# Extruder_0_Board.net
KiCad netlist of a schematic drawn in EAGLE
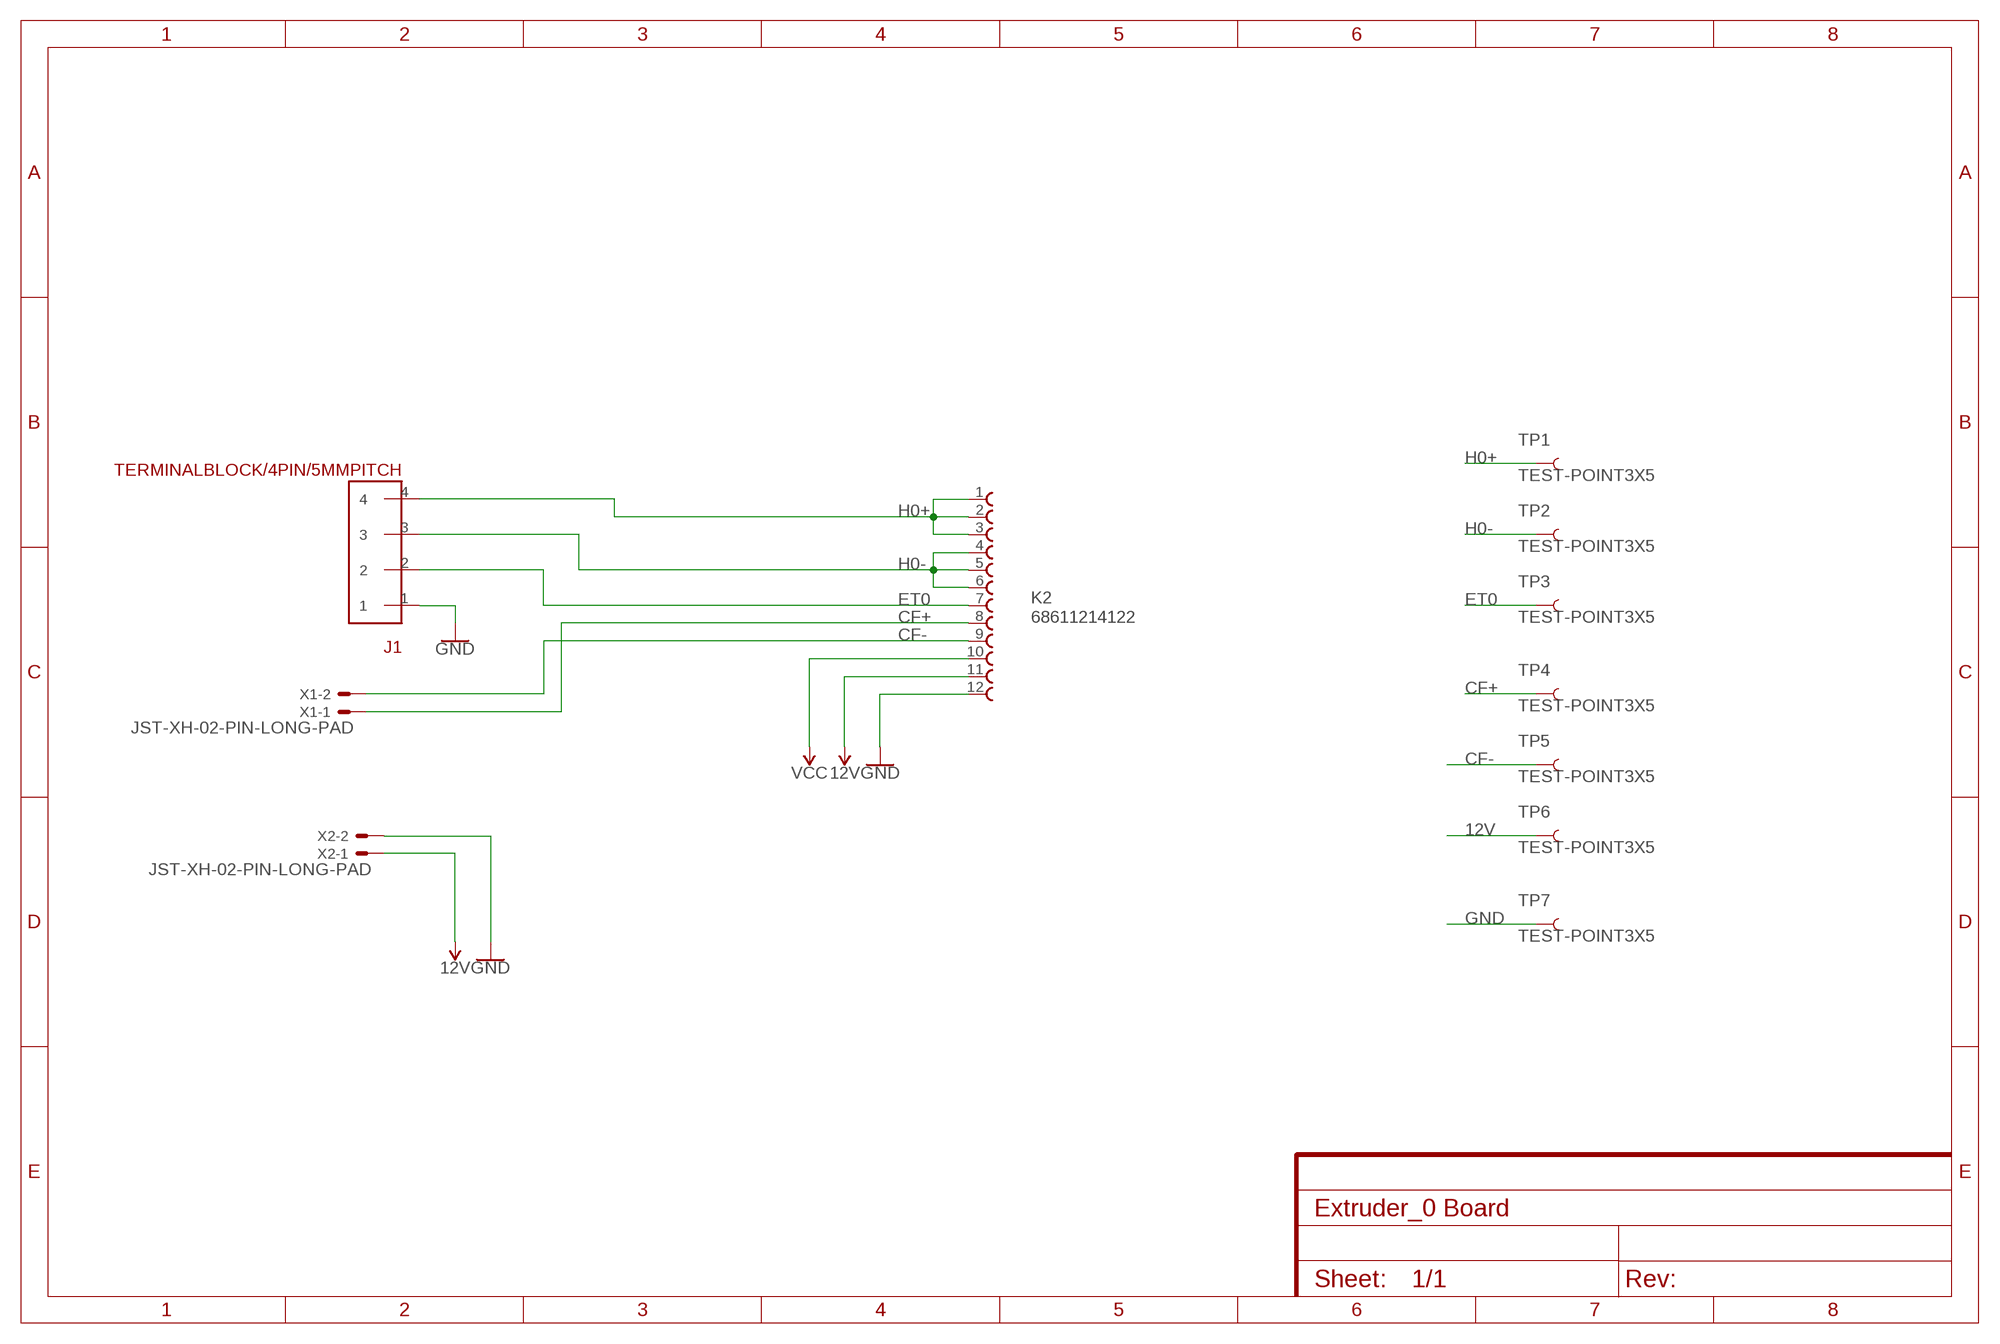
[diagram p0: schematic, sheet 1]

(export (version "E")
  (design (tool "Eeschema 10.0.6"))
  (components
    (comp (ref "J1")
      (value "TERMINALBLOCK/4PIN/5MMPITCH")
      (footprint "eagle-import:TERMINALBLOCK_TOYO_4PIN_5MMPITCH")
      (libsource (lib "eagle-import") (part "TERMINALBLOCK/4PIN/5MMPITCH"))
    )
    (comp (ref "K2")
      (value "68611214122")
      (footprint "eagle-import:68611214122")
      (libsource (lib "eagle-import") (part "68611214122"))
    )
    (comp (ref "TP1")
      (value "TEST-POINT3X5")
      (footprint "eagle-import:PAD.03X.05")
      (libsource (lib "eagle-import") (part "TEST-POINT3X5"))
    )
    (comp (ref "TP2")
      (value "TEST-POINT3X5")
      (footprint "eagle-import:PAD.03X.05")
      (libsource (lib "eagle-import") (part "TEST-POINT3X5"))
    )
    (comp (ref "TP3")
      (value "TEST-POINT3X5")
      (footprint "eagle-import:PAD.03X.05")
      (libsource (lib "eagle-import") (part "TEST-POINT3X5"))
    )
    (comp (ref "TP4")
      (value "TEST-POINT3X5")
      (footprint "eagle-import:PAD.03X.05")
      (libsource (lib "eagle-import") (part "TEST-POINT3X5"))
    )
    (comp (ref "TP5")
      (value "TEST-POINT3X5")
      (footprint "eagle-import:PAD.03X.05")
      (libsource (lib "eagle-import") (part "TEST-POINT3X5"))
    )
    (comp (ref "TP6")
      (value "TEST-POINT3X5")
      (footprint "eagle-import:PAD.03X.05")
      (libsource (lib "eagle-import") (part "TEST-POINT3X5"))
    )
    (comp (ref "TP7")
      (value "TEST-POINT3X5")
      (footprint "eagle-import:PAD.03X.05")
      (libsource (lib "eagle-import") (part "TEST-POINT3X5"))
    )
    (comp (ref "X1")
      (value "JST-XH-02-PIN-LONG-PAD")
      (footprint "eagle-import:JST-XH-02-PACKAGE-LONG-PAD")
      (libsource (lib "eagle-import") (part "JST-XH-02-PIN-LONG-PAD"))
    )
    (comp (ref "X2")
      (value "JST-XH-02-PIN-LONG-PAD")
      (footprint "eagle-import:JST-XH-02-PACKAGE-LONG-PAD")
      (libsource (lib "eagle-import") (part "JST-XH-02-PIN-LONG-PAD"))
    )
  )
  (nets
    (net (code "1") (name "/CF+") (class "Default")
      (node (ref "K2") (pin "8") (pinfunction "8_8") (pintype "passive"))
      (node (ref "TP4") (pin "P$1") (pinfunction "1_P$1") (pintype "bidirectional"))
      (node (ref "X1") (pin "1") (pinfunction "S_1") (pintype "passive"))
    )
    (net (code "2") (name "/CF-") (class "Default")
      (node (ref "K2") (pin "9") (pinfunction "9_9") (pintype "passive"))
      (node (ref "TP5") (pin "P$1") (pinfunction "1_P$1") (pintype "bidirectional"))
      (node (ref "X1") (pin "2") (pinfunction "S_2") (pintype "passive"))
    )
    (net (code "3") (name "/ET0") (class "Default")
      (node (ref "J1") (pin "2") (pinfunction "2_2") (pintype "bidirectional"))
      (node (ref "K2") (pin "7") (pinfunction "7_7") (pintype "passive"))
      (node (ref "TP3") (pin "P$1") (pinfunction "1_P$1") (pintype "bidirectional"))
    )
    (net (code "4") (name "/H0+") (class "Default")
      (node (ref "J1") (pin "4") (pinfunction "4_4") (pintype "bidirectional"))
      (node (ref "K2") (pin "1") (pinfunction "1_1") (pintype "passive"))
      (node (ref "K2") (pin "2") (pinfunction "2_2") (pintype "passive"))
      (node (ref "K2") (pin "3") (pinfunction "3_3") (pintype "passive"))
      (node (ref "TP1") (pin "P$1") (pinfunction "1_P$1") (pintype "bidirectional"))
    )
    (net (code "5") (name "/H0-") (class "Default")
      (node (ref "J1") (pin "3") (pinfunction "3_3") (pintype "bidirectional"))
      (node (ref "K2") (pin "4") (pinfunction "4_4") (pintype "passive"))
      (node (ref "K2") (pin "5") (pinfunction "5_5") (pintype "passive"))
      (node (ref "K2") (pin "6") (pinfunction "6_6") (pintype "passive"))
      (node (ref "TP2") (pin "P$1") (pinfunction "1_P$1") (pintype "bidirectional"))
    )
    (net (code "6") (name "12V") (class "Default")
      (node (ref "K2") (pin "11") (pinfunction "11_11") (pintype "passive"))
      (node (ref "TP6") (pin "P$1") (pinfunction "1_P$1") (pintype "bidirectional"))
      (node (ref "X2") (pin "1") (pinfunction "S_1") (pintype "passive"))
    )
    (net (code "7") (name "GND") (class "Default")
      (node (ref "J1") (pin "1") (pinfunction "1_1") (pintype "bidirectional"))
      (node (ref "K2") (pin "12") (pinfunction "12_12") (pintype "passive"))
      (node (ref "TP7") (pin "P$1") (pinfunction "1_P$1") (pintype "bidirectional"))
      (node (ref "X2") (pin "2") (pinfunction "S_2") (pintype "passive"))
    )
    (net (code "8") (name "VCC") (class "Default")
      (node (ref "K2") (pin "10") (pinfunction "10_10") (pintype "passive"))
    )
  )
)
